# XBee_Ctrl_No_Magnetometer.net
KiCad netlist of a schematic drawn in EAGLE
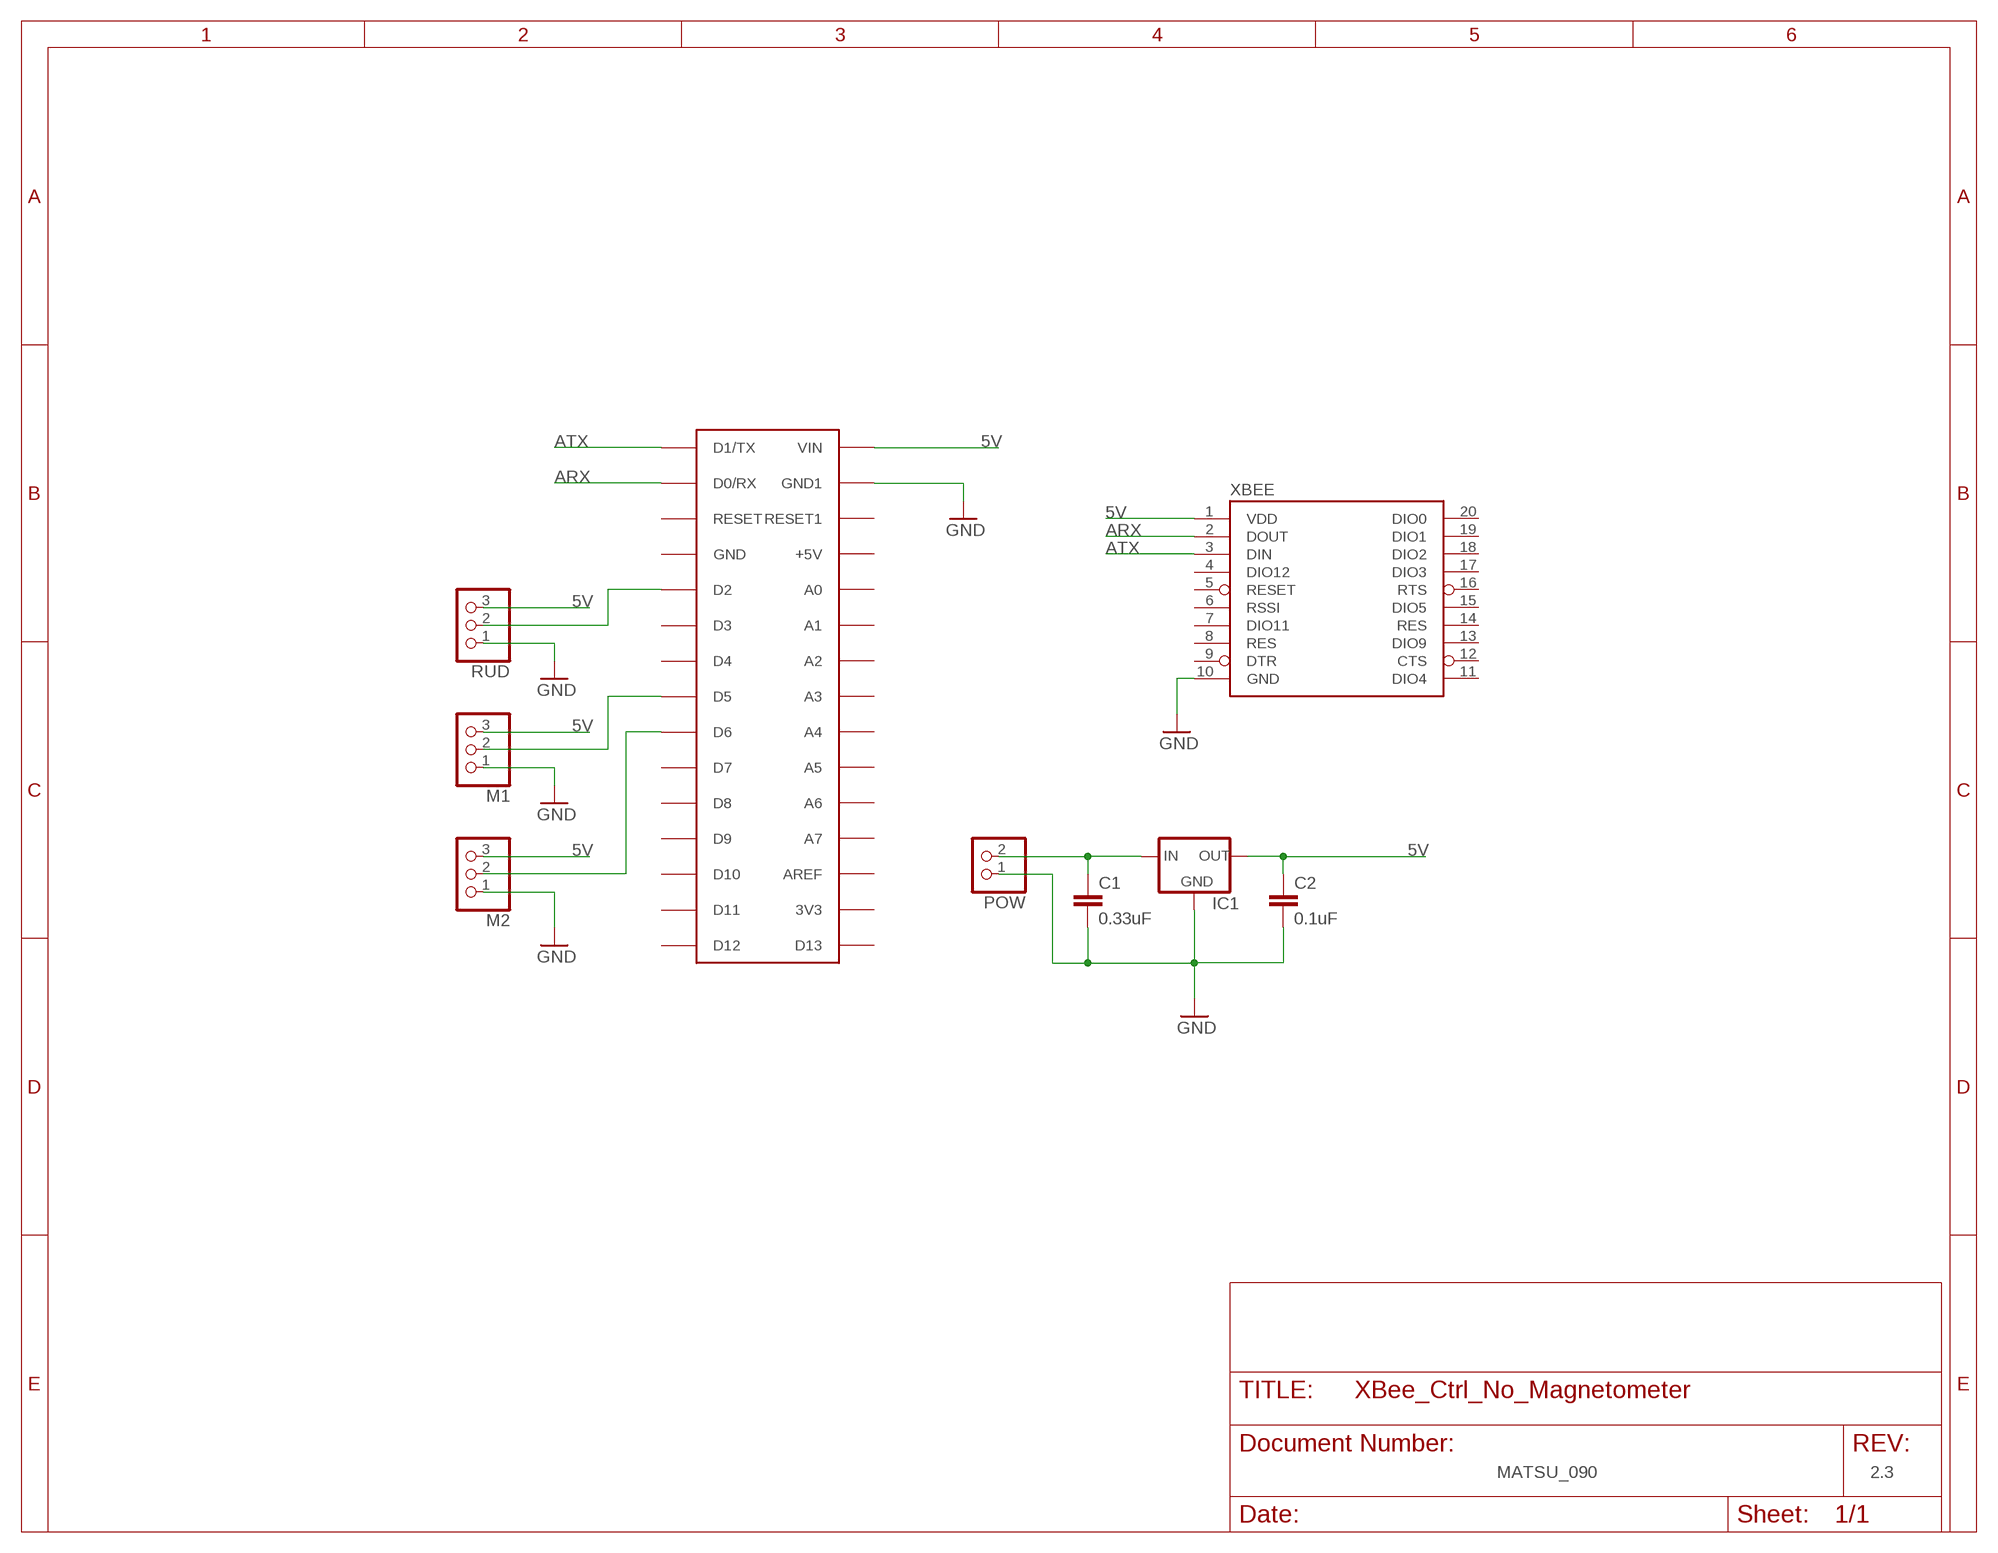
[diagram p0: schematic, sheet 1]

(export (version "E")
  (design (tool "Eeschema 10.0.6"))
  (components
    (comp (ref "C1")
      (value "0.33uF")
      (footprint "eagle-import:C5B2.5")
      (libsource (lib "eagle-import") (part "C5/2.5"))
    )
    (comp (ref "C2")
      (value "0.1uF")
      (footprint "eagle-import:C5B2.5")
      (libsource (lib "eagle-import") (part "C5/2.5"))
    )
    (comp (ref "IC1")
      (value "78XXL")
      (footprint "eagle-import:78XXL")
      (libsource (lib "eagle-import") (part "78XXL"))
    )
    (comp (ref "M1")
      (value "PINHD-1X3")
      (footprint "eagle-import:1X03")
      (libsource (lib "eagle-import") (part "PINHD-1X3"))
    )
    (comp (ref "M2")
      (value "PINHD-1X3")
      (footprint "eagle-import:1X03")
      (libsource (lib "eagle-import") (part "PINHD-1X3"))
    )
    (comp (ref "NANO")
      (value "ARDUINONANO")
      (footprint "eagle-import:PDIP-32")
      (libsource (lib "eagle-import") (part "ARDUINONANO"))
    )
    (comp (ref "POW")
      (value "PINHD-1X2")
      (footprint "eagle-import:1X02")
      (libsource (lib "eagle-import") (part "PINHD-1X2"))
    )
    (comp (ref "RUD")
      (value "PINHD-1X3")
      (footprint "eagle-import:1X03")
      (libsource (lib "eagle-import") (part "PINHD-1X3"))
    )
    (comp (ref "XBEE")
      (value "XBEE-1B1")
      (footprint "eagle-import:XBEE-1")
      (libsource (lib "eagle-import") (part "XBEE-1B1"))
    )
  )
  (nets
    (net (code "1") (name "/5V") (class "Default")
      (node (ref "C2") (pin "1") (pinfunction "1_1") (pintype "passive"))
      (node (ref "IC1") (pin "OUT") (pinfunction "OUT_OUT") (pintype "passive"))
      (node (ref "M1") (pin "3") (pinfunction "3_3") (pintype "passive"))
      (node (ref "M2") (pin "3") (pinfunction "3_3") (pintype "passive"))
      (node (ref "NANO") (pin "VIN") (pinfunction "VIN_VIN") (pintype "bidirectional"))
      (node (ref "RUD") (pin "3") (pinfunction "3_3") (pintype "passive"))
      (node (ref "XBEE") (pin "1") (pinfunction "VDD_1") (pintype "power_in"))
    )
    (net (code "2") (name "/ARX") (class "Default")
      (node (ref "NANO") (pin "D0/RX") (pinfunction "D0/RX_D0/RX") (pintype "bidirectional"))
      (node (ref "XBEE") (pin "2") (pinfunction "DOUT_2") (pintype "output"))
    )
    (net (code "3") (name "/ATX") (class "Default")
      (node (ref "NANO") (pin "D1/TX") (pinfunction "D1/TX_D1/TX") (pintype "bidirectional"))
      (node (ref "XBEE") (pin "3") (pinfunction "DIN_3") (pintype "input"))
    )
    (net (code "4") (name "GND") (class "Default")
      (node (ref "C1") (pin "2") (pinfunction "2_2") (pintype "passive"))
      (node (ref "C2") (pin "2") (pinfunction "2_2") (pintype "passive"))
      (node (ref "IC1") (pin "GND") (pinfunction "GND_GND") (pintype "input"))
      (node (ref "M1") (pin "1") (pinfunction "1_1") (pintype "passive"))
      (node (ref "M2") (pin "1") (pinfunction "1_1") (pintype "passive"))
      (node (ref "NANO") (pin "GND1") (pinfunction "GND1_GND1") (pintype "bidirectional"))
      (node (ref "POW") (pin "1") (pinfunction "1_1") (pintype "passive"))
      (node (ref "RUD") (pin "1") (pinfunction "1_1") (pintype "passive"))
      (node (ref "XBEE") (pin "10") (pinfunction "GND_10") (pintype "power_in"))
    )
    (net (code "5") (name "Net-(C1-Pad1)") (class "Default")
      (node (ref "C1") (pin "1") (pinfunction "1_1") (pintype "passive"))
      (node (ref "IC1") (pin "IN") (pinfunction "IN_IN") (pintype "input"))
      (node (ref "POW") (pin "2") (pinfunction "2_2") (pintype "passive"))
    )
    (net (code "6") (name "Net-(M1-Pad2)") (class "Default")
      (node (ref "M1") (pin "2") (pinfunction "2_2") (pintype "passive"))
      (node (ref "NANO") (pin "D5") (pinfunction "D5_D5") (pintype "bidirectional"))
    )
    (net (code "7") (name "Net-(M2-Pad2)") (class "Default")
      (node (ref "M2") (pin "2") (pinfunction "2_2") (pintype "passive"))
      (node (ref "NANO") (pin "D6") (pinfunction "D6_D6") (pintype "bidirectional"))
    )
    (net (code "8") (name "Net-(NANO-PadD2)") (class "Default")
      (node (ref "NANO") (pin "D2") (pinfunction "D2_D2") (pintype "bidirectional"))
      (node (ref "RUD") (pin "2") (pinfunction "2_2") (pintype "passive"))
    )
    (net (code "9") (name "unconnected-(NANO-Pad+5V)") (class "Default")
      (node (ref "NANO") (pin "+5V") (pinfunction "+5V_+5V") (pintype "bidirectional"))
    )
    (net (code "10") (name "unconnected-(NANO-Pad3V3)") (class "Default")
      (node (ref "NANO") (pin "3V3") (pinfunction "3V3_3V3") (pintype "bidirectional"))
    )
    (net (code "11") (name "unconnected-(NANO-PadA0)") (class "Default")
      (node (ref "NANO") (pin "A0") (pinfunction "A0_A0") (pintype "bidirectional"))
    )
    (net (code "12") (name "unconnected-(NANO-PadA1)") (class "Default")
      (node (ref "NANO") (pin "A1") (pinfunction "A1_A1") (pintype "bidirectional"))
    )
    (net (code "13") (name "unconnected-(NANO-PadA2)") (class "Default")
      (node (ref "NANO") (pin "A2") (pinfunction "A2_A2") (pintype "bidirectional"))
    )
    (net (code "14") (name "unconnected-(NANO-PadA3)") (class "Default")
      (node (ref "NANO") (pin "A3") (pinfunction "A3_A3") (pintype "bidirectional"))
    )
    (net (code "15") (name "unconnected-(NANO-PadA4)") (class "Default")
      (node (ref "NANO") (pin "A4") (pinfunction "A4_A4") (pintype "bidirectional"))
    )
    (net (code "16") (name "unconnected-(NANO-PadA5)") (class "Default")
      (node (ref "NANO") (pin "A5") (pinfunction "A5_A5") (pintype "bidirectional"))
    )
    (net (code "17") (name "unconnected-(NANO-PadA6)") (class "Default")
      (node (ref "NANO") (pin "A6") (pinfunction "A6_A6") (pintype "bidirectional"))
    )
    (net (code "18") (name "unconnected-(NANO-PadA7)") (class "Default")
      (node (ref "NANO") (pin "A7") (pinfunction "A7_A7") (pintype "bidirectional"))
    )
    (net (code "19") (name "unconnected-(NANO-PadAREF)") (class "Default")
      (node (ref "NANO") (pin "AREF") (pinfunction "AREF_AREF") (pintype "bidirectional"))
    )
    (net (code "20") (name "unconnected-(NANO-PadD3)") (class "Default")
      (node (ref "NANO") (pin "D3") (pinfunction "D3_D3") (pintype "bidirectional"))
    )
    (net (code "21") (name "unconnected-(NANO-PadD4)") (class "Default")
      (node (ref "NANO") (pin "D4") (pinfunction "D4_D4") (pintype "bidirectional"))
    )
    (net (code "22") (name "unconnected-(NANO-PadD7)") (class "Default")
      (node (ref "NANO") (pin "D7") (pinfunction "D7_D7") (pintype "bidirectional"))
    )
    (net (code "23") (name "unconnected-(NANO-PadD8)") (class "Default")
      (node (ref "NANO") (pin "D8") (pinfunction "D8_D8") (pintype "bidirectional"))
    )
    (net (code "24") (name "unconnected-(NANO-PadD9)") (class "Default")
      (node (ref "NANO") (pin "D9") (pinfunction "D9_D9") (pintype "bidirectional"))
    )
    (net (code "25") (name "unconnected-(NANO-PadD10)") (class "Default")
      (node (ref "NANO") (pin "D10") (pinfunction "D10_D10") (pintype "bidirectional"))
    )
    (net (code "26") (name "unconnected-(NANO-PadD11)") (class "Default")
      (node (ref "NANO") (pin "D11") (pinfunction "D11_D11") (pintype "bidirectional"))
    )
    (net (code "27") (name "unconnected-(NANO-PadD12)") (class "Default")
      (node (ref "NANO") (pin "D12") (pinfunction "D12_D12") (pintype "bidirectional"))
    )
    (net (code "28") (name "unconnected-(NANO-PadD13)") (class "Default")
      (node (ref "NANO") (pin "D13") (pinfunction "D13_D13") (pintype "bidirectional"))
    )
    (net (code "29") (name "unconnected-(NANO-PadGND)") (class "Default")
      (node (ref "NANO") (pin "GND") (pinfunction "GND_GND") (pintype "bidirectional"))
    )
    (net (code "30") (name "unconnected-(NANO-PadRESET)") (class "Default")
      (node (ref "NANO") (pin "RESET") (pinfunction "RESET_RESET") (pintype "bidirectional"))
    )
    (net (code "31") (name "unconnected-(NANO-PadRESET1)") (class "Default")
      (node (ref "NANO") (pin "RESET1") (pinfunction "RESET1_RESET1") (pintype "bidirectional"))
    )
    (net (code "32") (name "unconnected-(XBEE-CTS-Pad12)") (class "Default")
      (node (ref "XBEE") (pin "12") (pinfunction "CTS_12") (pintype "output"))
    )
    (net (code "33") (name "unconnected-(XBEE-DIO0-Pad20)") (class "Default")
      (node (ref "XBEE") (pin "20") (pinfunction "DIO0_20") (pintype "bidirectional"))
    )
    (net (code "34") (name "unconnected-(XBEE-DIO1-Pad19)") (class "Default")
      (node (ref "XBEE") (pin "19") (pinfunction "DIO1_19") (pintype "bidirectional"))
    )
    (net (code "35") (name "unconnected-(XBEE-DIO2-Pad18)") (class "Default")
      (node (ref "XBEE") (pin "18") (pinfunction "DIO2_18") (pintype "bidirectional"))
    )
    (net (code "36") (name "unconnected-(XBEE-DIO3-Pad17)") (class "Default")
      (node (ref "XBEE") (pin "17") (pinfunction "DIO3_17") (pintype "bidirectional"))
    )
    (net (code "37") (name "unconnected-(XBEE-DIO4-Pad11)") (class "Default")
      (node (ref "XBEE") (pin "11") (pinfunction "DIO4_11") (pintype "bidirectional"))
    )
    (net (code "38") (name "unconnected-(XBEE-DIO5-Pad15)") (class "Default")
      (node (ref "XBEE") (pin "15") (pinfunction "DIO5_15") (pintype "bidirectional"))
    )
    (net (code "39") (name "unconnected-(XBEE-DIO9-Pad13)") (class "Default")
      (node (ref "XBEE") (pin "13") (pinfunction "DIO9_13") (pintype "bidirectional"))
    )
    (net (code "40") (name "unconnected-(XBEE-DIO11-Pad7)") (class "Default")
      (node (ref "XBEE") (pin "7") (pinfunction "DIO11_7") (pintype "bidirectional"))
    )
    (net (code "41") (name "unconnected-(XBEE-DIO12-Pad4)") (class "Default")
      (node (ref "XBEE") (pin "4") (pinfunction "DIO12_4") (pintype "bidirectional"))
    )
    (net (code "42") (name "unconnected-(XBEE-DTR-Pad9)") (class "Default")
      (node (ref "XBEE") (pin "9") (pinfunction "DTR_9") (pintype "bidirectional"))
    )
    (net (code "43") (name "unconnected-(XBEE-RES-Pad8)") (class "Default")
      (node (ref "XBEE") (pin "8") (pinfunction "RES_8") (pintype "bidirectional"))
    )
    (net (code "44") (name "unconnected-(XBEE-RES-Pad14)") (class "Default")
      (node (ref "XBEE") (pin "14") (pinfunction "RES_14") (pintype "bidirectional"))
    )
    (net (code "45") (name "unconnected-(XBEE-RESET-Pad5)") (class "Default")
      (node (ref "XBEE") (pin "5") (pinfunction "RESET_5") (pintype "input"))
    )
    (net (code "46") (name "unconnected-(XBEE-RSSI-Pad6)") (class "Default")
      (node (ref "XBEE") (pin "6") (pinfunction "RSSI_6") (pintype "bidirectional"))
    )
    (net (code "47") (name "unconnected-(XBEE-RTS-Pad16)") (class "Default")
      (node (ref "XBEE") (pin "16") (pinfunction "RTS_16") (pintype "input"))
    )
  )
)
